# led_board.net
KiCad netlist of a schematic drawn in EAGLE
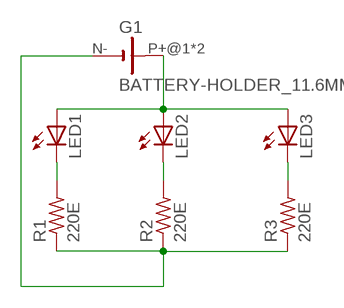
[diagram p0: schematic, sheet 1]

(export (version "E")
  (design (tool "Eeschema 10.0.6"))
  (components
    (comp (ref "G1")
      (value "BATTERY-HOLDER_11.6MM")
      (footprint "eagle-import:CELL_RETAINER_11.6MM")
      (fields (field (name "MF") "KEYSTONE") (field (name "MPN") "2997"))
      (libsource (lib "eagle-import") (part "BATTERY-HOLDER_11.6MM"))
    )
    (comp (ref "LED1")
      (value "LED5MM")
      (footprint "eagle-import:LED5MM")
      (libsource (lib "eagle-import") (part "LED5MM"))
    )
    (comp (ref "LED2")
      (value "LED5MM")
      (footprint "eagle-import:LED5MM")
      (libsource (lib "eagle-import") (part "LED5MM"))
    )
    (comp (ref "LED3")
      (value "LED5MM")
      (footprint "eagle-import:LED5MM")
      (libsource (lib "eagle-import") (part "LED5MM"))
    )
    (comp (ref "R1")
      (value "220E")
      (footprint "eagle-import:0207_2V")
      (libsource (lib "eagle-import") (part "R-US_0207/2V"))
    )
    (comp (ref "R2")
      (value "220E")
      (footprint "eagle-import:0207_2V")
      (libsource (lib "eagle-import") (part "R-US_0207/2V"))
    )
    (comp (ref "R3")
      (value "220E")
      (footprint "eagle-import:0207_2V")
      (libsource (lib "eagle-import") (part "R-US_0207/2V"))
    )
  )
  (nets
    (net (code "1") (name "Net-(G1-+-PadP+@1)") (class "Default")
      (node (ref "G1") (pin "P+@1") (pinfunction "+_P+@1") (pintype "passive"))
      (node (ref "G1") (pin "P+@2") (pinfunction "+_P+@2") (pintype "passive"))
      (node (ref "LED1") (pin "A") (pinfunction "A_A") (pintype "passive"))
      (node (ref "LED2") (pin "A") (pinfunction "A_A") (pintype "passive"))
      (node (ref "LED3") (pin "A") (pinfunction "A_A") (pintype "passive"))
    )
    (net (code "2") (name "Net-(G1--)") (class "Default")
      (node (ref "G1") (pin "N-") (pinfunction "-_N-") (pintype "passive"))
      (node (ref "R1") (pin "1") (pinfunction "1_1") (pintype "passive"))
      (node (ref "R2") (pin "1") (pinfunction "1_1") (pintype "passive"))
      (node (ref "R3") (pin "1") (pinfunction "1_1") (pintype "passive"))
    )
    (net (code "3") (name "Net-(LED1-C)") (class "Default")
      (node (ref "LED1") (pin "K") (pinfunction "C_K") (pintype "passive"))
      (node (ref "R1") (pin "2") (pinfunction "2_2") (pintype "passive"))
    )
    (net (code "4") (name "Net-(LED2-C)") (class "Default")
      (node (ref "LED2") (pin "K") (pinfunction "C_K") (pintype "passive"))
      (node (ref "R2") (pin "2") (pinfunction "2_2") (pintype "passive"))
    )
    (net (code "5") (name "Net-(LED3-C)") (class "Default")
      (node (ref "LED3") (pin "K") (pinfunction "C_K") (pintype "passive"))
      (node (ref "R3") (pin "2") (pinfunction "2_2") (pintype "passive"))
    )
  )
)
